# 04B-350.net
KiCad netlist of a schematic drawn in EAGLE
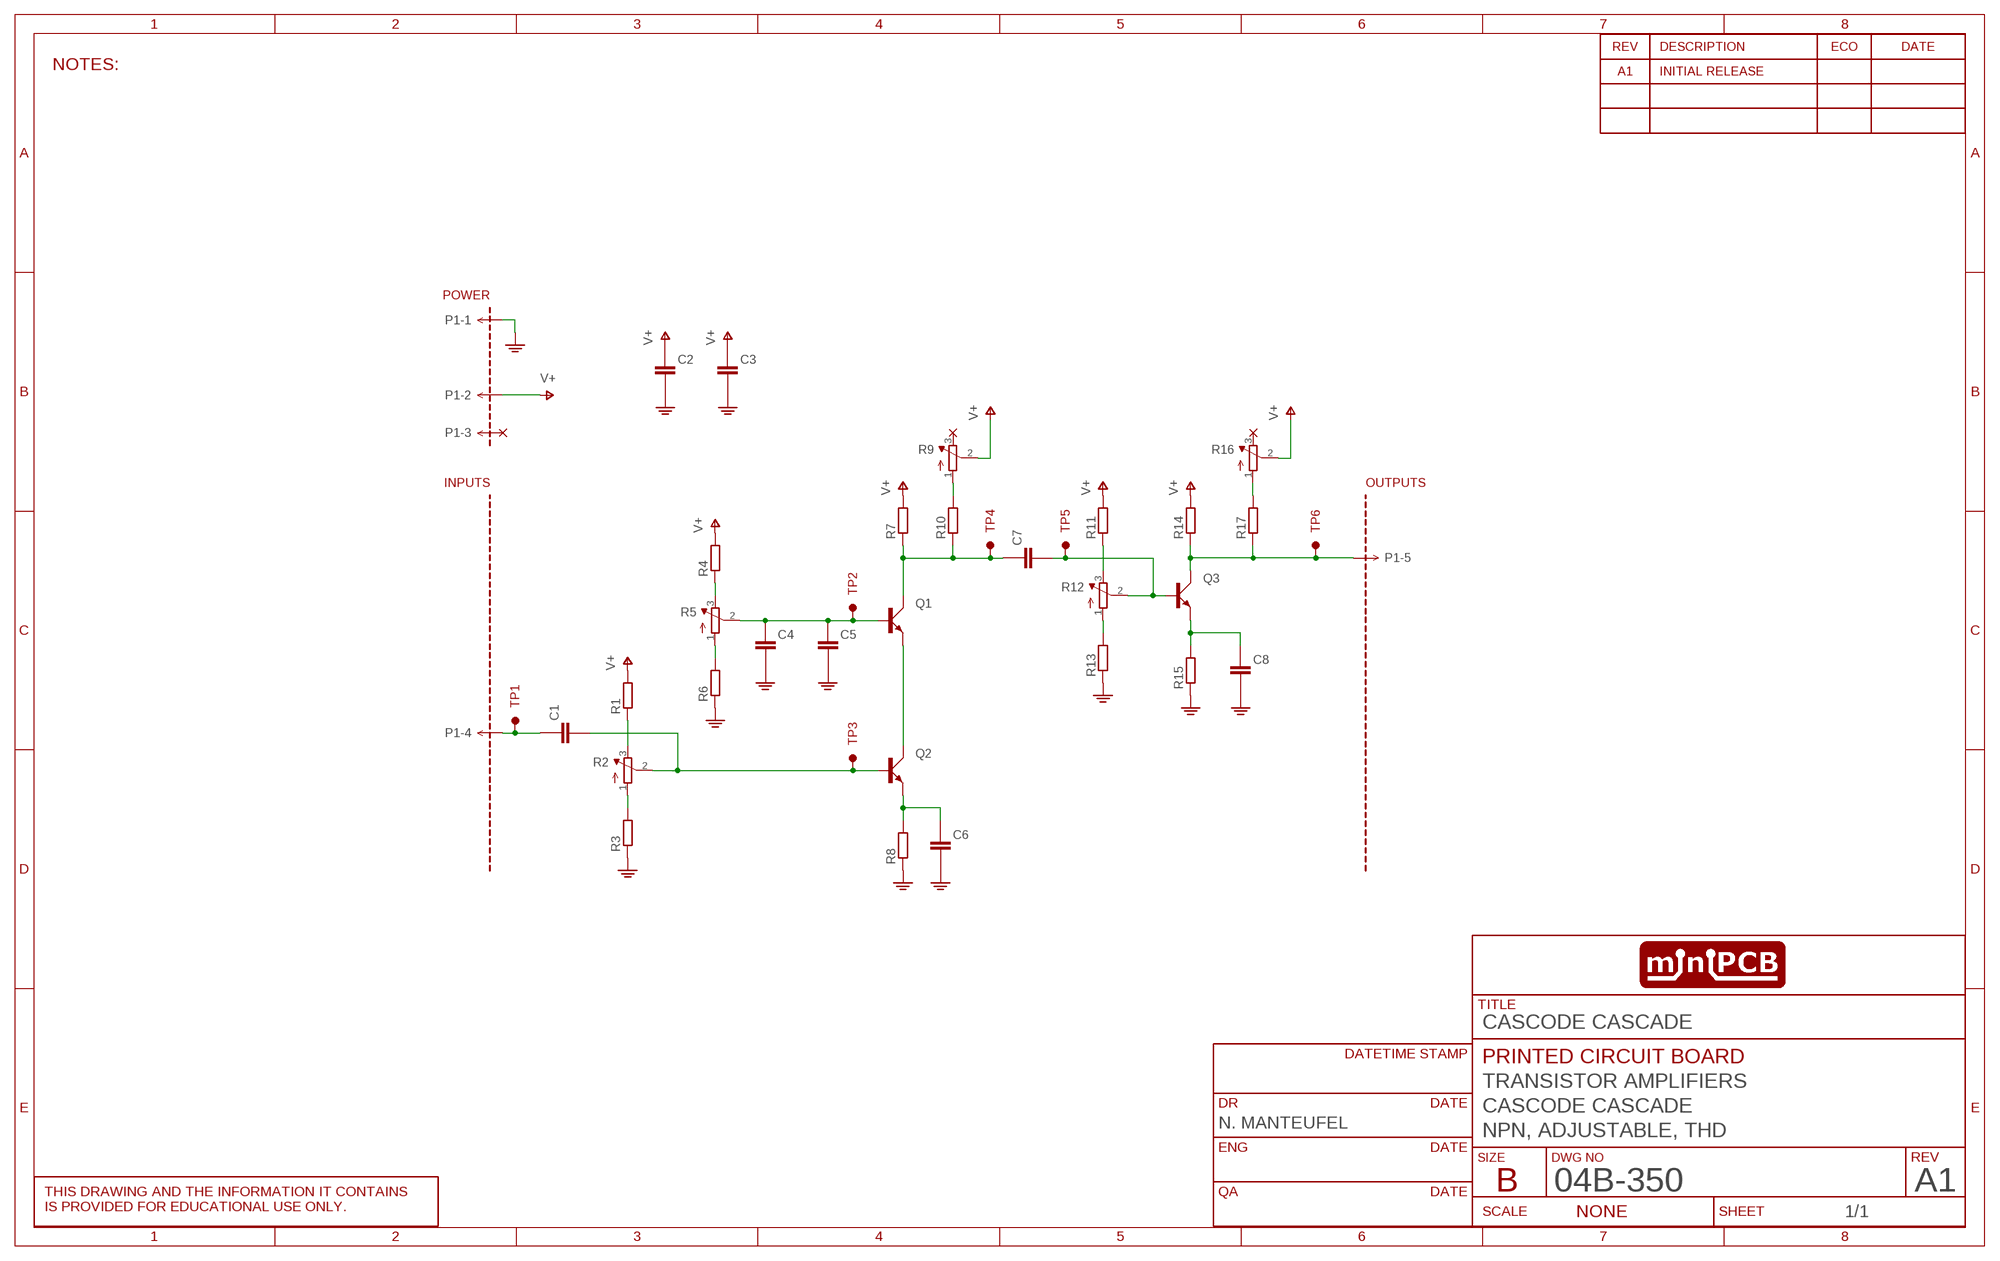
[diagram p0: schematic, sheet 1]

(export (version "E")
  (design (tool "Eeschema 10.0.6"))
  (components
    (comp (ref "C1")
      (value "CAPACITORTHD")
      (footprint "eagle-import:C050-024X044")
      (libsource (lib "eagle-import") (part "CAPACITORTHD"))
    )
    (comp (ref "C2")
      (value "CAPACITORTHD")
      (footprint "eagle-import:C050-024X044")
      (libsource (lib "eagle-import") (part "CAPACITORTHD"))
    )
    (comp (ref "C3")
      (value "CAPACITOR_10")
      (footprint "eagle-import:C5MM")
      (libsource (lib "eagle-import") (part "CAPACITOR_10"))
    )
    (comp (ref "C4")
      (value "CAPACITOR_10")
      (footprint "eagle-import:C5MM")
      (libsource (lib "eagle-import") (part "CAPACITOR_10"))
    )
    (comp (ref "C5")
      (value "CAPACITORTHD")
      (footprint "eagle-import:C050-024X044")
      (libsource (lib "eagle-import") (part "CAPACITORTHD"))
    )
    (comp (ref "C6")
      (value "CAPACITOR_10")
      (footprint "eagle-import:C5MM")
      (libsource (lib "eagle-import") (part "CAPACITOR_10"))
    )
    (comp (ref "C7")
      (value "CAPACITORTHD")
      (footprint "eagle-import:C050-024X044")
      (libsource (lib "eagle-import") (part "CAPACITORTHD"))
    )
    (comp (ref "C8")
      (value "CAPACITOR_10")
      (footprint "eagle-import:C5MM")
      (libsource (lib "eagle-import") (part "CAPACITOR_10"))
    )
    (comp (ref "P1")
      (value "MINIPCB_5P5P")
      (footprint "eagle-import:PINS_1X5")
      (libsource (lib "eagle-import") (part "MINIPCB_5P5P"))
    )
    (comp (ref "PCB1")
      (value "MINIPCB_0P50X75")
      (footprint "eagle-import:MINIPCB_0P_50X75")
      (fields
        (field (name "CIRCUIT_CATEGORY") "TRANSISTOR AMPLIFIERS")
        (field (name "PART_NUMBER") "04B-350")
        (field (name "REVISION") "A1-01")
        (field (name "TITLE") "CASCODE CASCADE AMPLIFIER")
      )
      (libsource (lib "eagle-import") (part "MINIPCB_0P50X75"))
    )
    (comp (ref "Q1")
      (value "BJT_NPNEBC")
      (footprint "eagle-import:TO92-EBC-OVAL")
      (libsource (lib "eagle-import") (part "BJT_NPNEBC"))
    )
    (comp (ref "Q2")
      (value "BJT_NPNEBC")
      (footprint "eagle-import:TO92-EBC-OVAL")
      (libsource (lib "eagle-import") (part "BJT_NPNEBC"))
    )
    (comp (ref "Q3")
      (value "BJT_NPNEBC")
      (footprint "eagle-import:TO92-EBC-OVAL")
      (libsource (lib "eagle-import") (part "BJT_NPNEBC"))
    )
    (comp (ref "R1")
      (value "RESISTORTHD")
      (footprint "eagle-import:0204_10")
      (libsource (lib "eagle-import") (part "RESISTORTHD"))
    )
    (comp (ref "R2")
      (value "TRIMPOT0.100THD")
      (footprint "eagle-import:TRIM_0100")
      (libsource (lib "eagle-import") (part "TRIMPOT0.100THD"))
    )
    (comp (ref "R3")
      (value "RESISTORTHD")
      (footprint "eagle-import:0204_10")
      (libsource (lib "eagle-import") (part "RESISTORTHD"))
    )
    (comp (ref "R4")
      (value "RESISTORTHD")
      (footprint "eagle-import:0204_10")
      (libsource (lib "eagle-import") (part "RESISTORTHD"))
    )
    (comp (ref "R5")
      (value "TRIMPOT0.100THD")
      (footprint "eagle-import:TRIM_0100")
      (libsource (lib "eagle-import") (part "TRIMPOT0.100THD"))
    )
    (comp (ref "R6")
      (value "RESISTORTHD")
      (footprint "eagle-import:0204_10")
      (libsource (lib "eagle-import") (part "RESISTORTHD"))
    )
    (comp (ref "R7")
      (value "RESISTORTHD")
      (footprint "eagle-import:0204_10")
      (libsource (lib "eagle-import") (part "RESISTORTHD"))
    )
    (comp (ref "R8")
      (value "RESISTORTHD")
      (footprint "eagle-import:0204_10")
      (libsource (lib "eagle-import") (part "RESISTORTHD"))
    )
    (comp (ref "R9")
      (value "TRIMPOT0.100THD")
      (footprint "eagle-import:TRIM_0100")
      (libsource (lib "eagle-import") (part "TRIMPOT0.100THD"))
    )
    (comp (ref "R10")
      (value "RESISTORTHD")
      (footprint "eagle-import:0204_10")
      (libsource (lib "eagle-import") (part "RESISTORTHD"))
    )
    (comp (ref "R11")
      (value "RESISTORTHD")
      (footprint "eagle-import:0204_10")
      (libsource (lib "eagle-import") (part "RESISTORTHD"))
    )
    (comp (ref "R12")
      (value "TRIMPOT0.100THD")
      (footprint "eagle-import:TRIM_0100")
      (libsource (lib "eagle-import") (part "TRIMPOT0.100THD"))
    )
    (comp (ref "R13")
      (value "RESISTORTHD")
      (footprint "eagle-import:0204_10")
      (libsource (lib "eagle-import") (part "RESISTORTHD"))
    )
    (comp (ref "R14")
      (value "RESISTORTHD")
      (footprint "eagle-import:0204_10")
      (libsource (lib "eagle-import") (part "RESISTORTHD"))
    )
    (comp (ref "R15")
      (value "RESISTORTHD")
      (footprint "eagle-import:0204_10")
      (libsource (lib "eagle-import") (part "RESISTORTHD"))
    )
    (comp (ref "R16")
      (value "TRIMPOT0.100THD")
      (footprint "eagle-import:TRIM_0100")
      (libsource (lib "eagle-import") (part "TRIMPOT0.100THD"))
    )
    (comp (ref "R17")
      (value "RESISTORTHD")
      (footprint "eagle-import:0204_10")
      (libsource (lib "eagle-import") (part "RESISTORTHD"))
    )
    (comp (ref "TP1")
      (value "TESTPOINTKE5000-SMTEXT")
      (footprint "eagle-import:PINS_1_TESTPOINT_KE5000_NOTEXT")
      (libsource (lib "eagle-import") (part "TESTPOINTKE5000-SMTEXT"))
    )
    (comp (ref "TP2")
      (value "TESTPOINTKE5000-SMTEXT")
      (footprint "eagle-import:PINS_1_TESTPOINT_KE5000_NOTEXT")
      (libsource (lib "eagle-import") (part "TESTPOINTKE5000-SMTEXT"))
    )
    (comp (ref "TP3")
      (value "TESTPOINTKE5000-SMTEXT")
      (footprint "eagle-import:PINS_1_TESTPOINT_KE5000_NOTEXT")
      (libsource (lib "eagle-import") (part "TESTPOINTKE5000-SMTEXT"))
    )
    (comp (ref "TP4")
      (value "TESTPOINTKE5000-SMTEXT")
      (footprint "eagle-import:PINS_1_TESTPOINT_KE5000_NOTEXT")
      (libsource (lib "eagle-import") (part "TESTPOINTKE5000-SMTEXT"))
    )
    (comp (ref "TP5")
      (value "TESTPOINTKE5000-SMTEXT")
      (footprint "eagle-import:PINS_1_TESTPOINT_KE5000_NOTEXT")
      (libsource (lib "eagle-import") (part "TESTPOINTKE5000-SMTEXT"))
    )
    (comp (ref "TP6")
      (value "TESTPOINTKE5000-SMTEXT")
      (footprint "eagle-import:PINS_1_TESTPOINT_KE5000_NOTEXT")
      (libsource (lib "eagle-import") (part "TESTPOINTKE5000-SMTEXT"))
    )
  )
  (nets
    (net (code "1") (name "GND") (class "Default")
      (node (ref "C2") (pin "2") (pinfunction "-_2") (pintype "passive"))
      (node (ref "C3") (pin "-") (pinfunction "-_-") (pintype "passive"))
      (node (ref "C4") (pin "-") (pinfunction "-_-") (pintype "passive"))
      (node (ref "C5") (pin "2") (pinfunction "-_2") (pintype "passive"))
      (node (ref "C6") (pin "-") (pinfunction "-_-") (pintype "passive"))
      (node (ref "C8") (pin "-") (pinfunction "-_-") (pintype "passive"))
      (node (ref "P1") (pin "1") (pinfunction "1_1") (pintype "bidirectional"))
      (node (ref "R13") (pin "1") (pinfunction "1_1") (pintype "passive"))
      (node (ref "R15") (pin "1") (pinfunction "1_1") (pintype "passive"))
      (node (ref "R3") (pin "1") (pinfunction "1_1") (pintype "passive"))
      (node (ref "R6") (pin "1") (pinfunction "1_1") (pintype "passive"))
      (node (ref "R8") (pin "1") (pinfunction "1_1") (pintype "passive"))
    )
    (net (code "2") (name "Net-(C1-+)") (class "Default")
      (node (ref "C1") (pin "1") (pinfunction "+_1") (pintype "passive"))
      (node (ref "P1") (pin "4") (pinfunction "1_4") (pintype "bidirectional"))
      (node (ref "TP1") (pin "1") (pinfunction "1_1") (pintype "bidirectional"))
    )
    (net (code "3") (name "Net-(C1--)") (class "Default")
      (node (ref "C1") (pin "2") (pinfunction "-_2") (pintype "passive"))
      (node (ref "Q2") (pin "B") (pinfunction "B_B") (pintype "passive"))
      (node (ref "R2") (pin "2") (pinfunction "S_2") (pintype "passive"))
      (node (ref "TP3") (pin "1") (pinfunction "1_1") (pintype "bidirectional"))
    )
    (net (code "4") (name "Net-(C5-+)") (class "Default")
      (node (ref "C4") (pin "+") (pinfunction "+_+") (pintype "passive"))
      (node (ref "C5") (pin "1") (pinfunction "+_1") (pintype "passive"))
      (node (ref "Q1") (pin "B") (pinfunction "B_B") (pintype "passive"))
      (node (ref "R5") (pin "2") (pinfunction "S_2") (pintype "passive"))
      (node (ref "TP2") (pin "1") (pinfunction "1_1") (pintype "bidirectional"))
    )
    (net (code "5") (name "Net-(C6-Pad+)") (class "Default")
      (node (ref "C6") (pin "+") (pinfunction "+_+") (pintype "passive"))
      (node (ref "Q2") (pin "E") (pinfunction "E_E") (pintype "passive"))
      (node (ref "R8") (pin "2") (pinfunction "2_2") (pintype "passive"))
    )
    (net (code "6") (name "Net-(C7-+)") (class "Default")
      (node (ref "C7") (pin "1") (pinfunction "+_1") (pintype "passive"))
      (node (ref "Q1") (pin "C") (pinfunction "C_C") (pintype "passive"))
      (node (ref "R10") (pin "1") (pinfunction "1_1") (pintype "passive"))
      (node (ref "R7") (pin "1") (pinfunction "1_1") (pintype "passive"))
      (node (ref "TP4") (pin "1") (pinfunction "1_1") (pintype "bidirectional"))
    )
    (net (code "7") (name "Net-(C7--)") (class "Default")
      (node (ref "C7") (pin "2") (pinfunction "-_2") (pintype "passive"))
      (node (ref "Q3") (pin "B") (pinfunction "B_B") (pintype "passive"))
      (node (ref "R12") (pin "2") (pinfunction "S_2") (pintype "passive"))
      (node (ref "TP5") (pin "1") (pinfunction "1_1") (pintype "bidirectional"))
    )
    (net (code "8") (name "Net-(C8-Pad+)") (class "Default")
      (node (ref "C8") (pin "+") (pinfunction "+_+") (pintype "passive"))
      (node (ref "Q3") (pin "E") (pinfunction "E_E") (pintype "passive"))
      (node (ref "R15") (pin "2") (pinfunction "2_2") (pintype "passive"))
    )
    (net (code "9") (name "Net-(P1E-1)") (class "Default")
      (node (ref "P1") (pin "5") (pinfunction "1_5") (pintype "bidirectional"))
      (node (ref "Q3") (pin "C") (pinfunction "C_C") (pintype "passive"))
      (node (ref "R14") (pin "1") (pinfunction "1_1") (pintype "passive"))
      (node (ref "R17") (pin "1") (pinfunction "1_1") (pintype "passive"))
      (node (ref "TP6") (pin "1") (pinfunction "1_1") (pintype "bidirectional"))
    )
    (net (code "10") (name "Net-(Q1-PadE)") (class "Default")
      (node (ref "Q1") (pin "E") (pinfunction "E_E") (pintype "passive"))
      (node (ref "Q2") (pin "C") (pinfunction "C_C") (pintype "passive"))
    )
    (net (code "11") (name "Net-(R2-A)") (class "Default")
      (node (ref "R2") (pin "1") (pinfunction "A_1") (pintype "passive"))
      (node (ref "R3") (pin "2") (pinfunction "2_2") (pintype "passive"))
    )
    (net (code "12") (name "Net-(R2-E)") (class "Default")
      (node (ref "R1") (pin "1") (pinfunction "1_1") (pintype "passive"))
      (node (ref "R2") (pin "3") (pinfunction "E_3") (pintype "passive"))
    )
    (net (code "13") (name "Net-(R5-A)") (class "Default")
      (node (ref "R5") (pin "1") (pinfunction "A_1") (pintype "passive"))
      (node (ref "R6") (pin "2") (pinfunction "2_2") (pintype "passive"))
    )
    (net (code "14") (name "Net-(R5-E)") (class "Default")
      (node (ref "R4") (pin "1") (pinfunction "1_1") (pintype "passive"))
      (node (ref "R5") (pin "3") (pinfunction "E_3") (pintype "passive"))
    )
    (net (code "15") (name "Net-(R9-A)") (class "Default")
      (node (ref "R10") (pin "2") (pinfunction "2_2") (pintype "passive"))
      (node (ref "R9") (pin "1") (pinfunction "A_1") (pintype "passive"))
    )
    (net (code "16") (name "Net-(R12-A)") (class "Default")
      (node (ref "R12") (pin "1") (pinfunction "A_1") (pintype "passive"))
      (node (ref "R13") (pin "2") (pinfunction "2_2") (pintype "passive"))
    )
    (net (code "17") (name "Net-(R12-E)") (class "Default")
      (node (ref "R11") (pin "1") (pinfunction "1_1") (pintype "passive"))
      (node (ref "R12") (pin "3") (pinfunction "E_3") (pintype "passive"))
    )
    (net (code "18") (name "Net-(R16-A)") (class "Default")
      (node (ref "R16") (pin "1") (pinfunction "A_1") (pintype "passive"))
      (node (ref "R17") (pin "2") (pinfunction "2_2") (pintype "passive"))
    )
    (net (code "19") (name "V+") (class "Default")
      (node (ref "C2") (pin "1") (pinfunction "+_1") (pintype "passive"))
      (node (ref "C3") (pin "+") (pinfunction "+_+") (pintype "passive"))
      (node (ref "P1") (pin "2") (pinfunction "1_2") (pintype "bidirectional"))
      (node (ref "R1") (pin "2") (pinfunction "2_2") (pintype "passive"))
      (node (ref "R11") (pin "2") (pinfunction "2_2") (pintype "passive"))
      (node (ref "R14") (pin "2") (pinfunction "2_2") (pintype "passive"))
      (node (ref "R16") (pin "2") (pinfunction "S_2") (pintype "passive"))
      (node (ref "R4") (pin "2") (pinfunction "2_2") (pintype "passive"))
      (node (ref "R7") (pin "2") (pinfunction "2_2") (pintype "passive"))
      (node (ref "R9") (pin "2") (pinfunction "S_2") (pintype "passive"))
    )
    (net (code "20") (name "unconnected-(P1C-1-Pad3)") (class "Default")
      (node (ref "P1") (pin "3") (pinfunction "1_3") (pintype "bidirectional"))
    )
    (net (code "21") (name "unconnected-(R9-E-Pad3)") (class "Default")
      (node (ref "R9") (pin "3") (pinfunction "E_3") (pintype "passive"))
    )
    (net (code "22") (name "unconnected-(R16-E-Pad3)") (class "Default")
      (node (ref "R16") (pin "3") (pinfunction "E_3") (pintype "passive"))
    )
  )
)
